# Drone-dimension.net
KiCad netlist of a schematic drawn in EAGLE
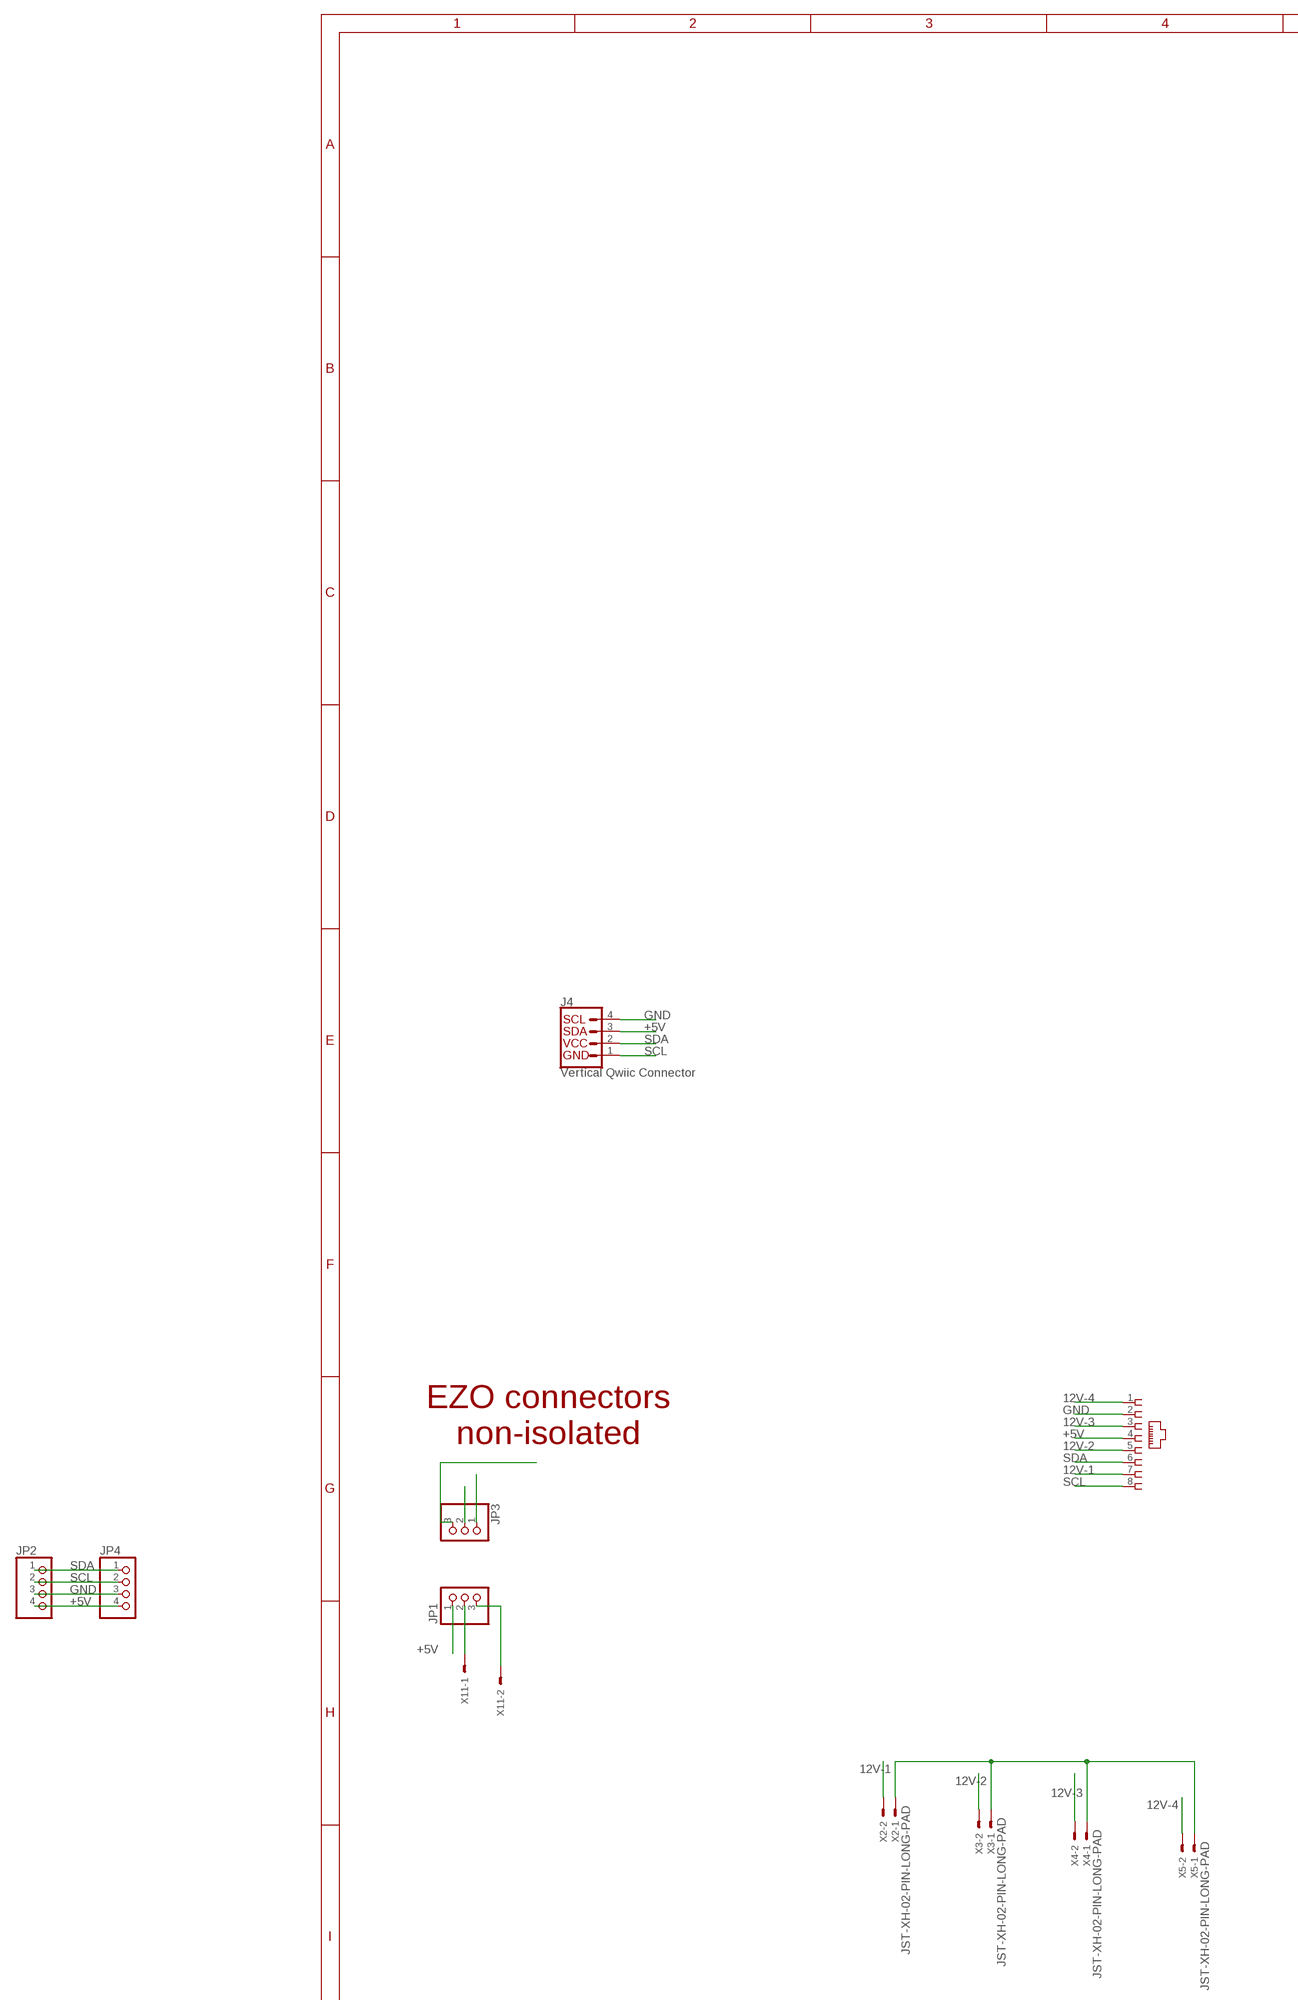
[diagram p0: schematic, sheet 1, part 1 of 2]
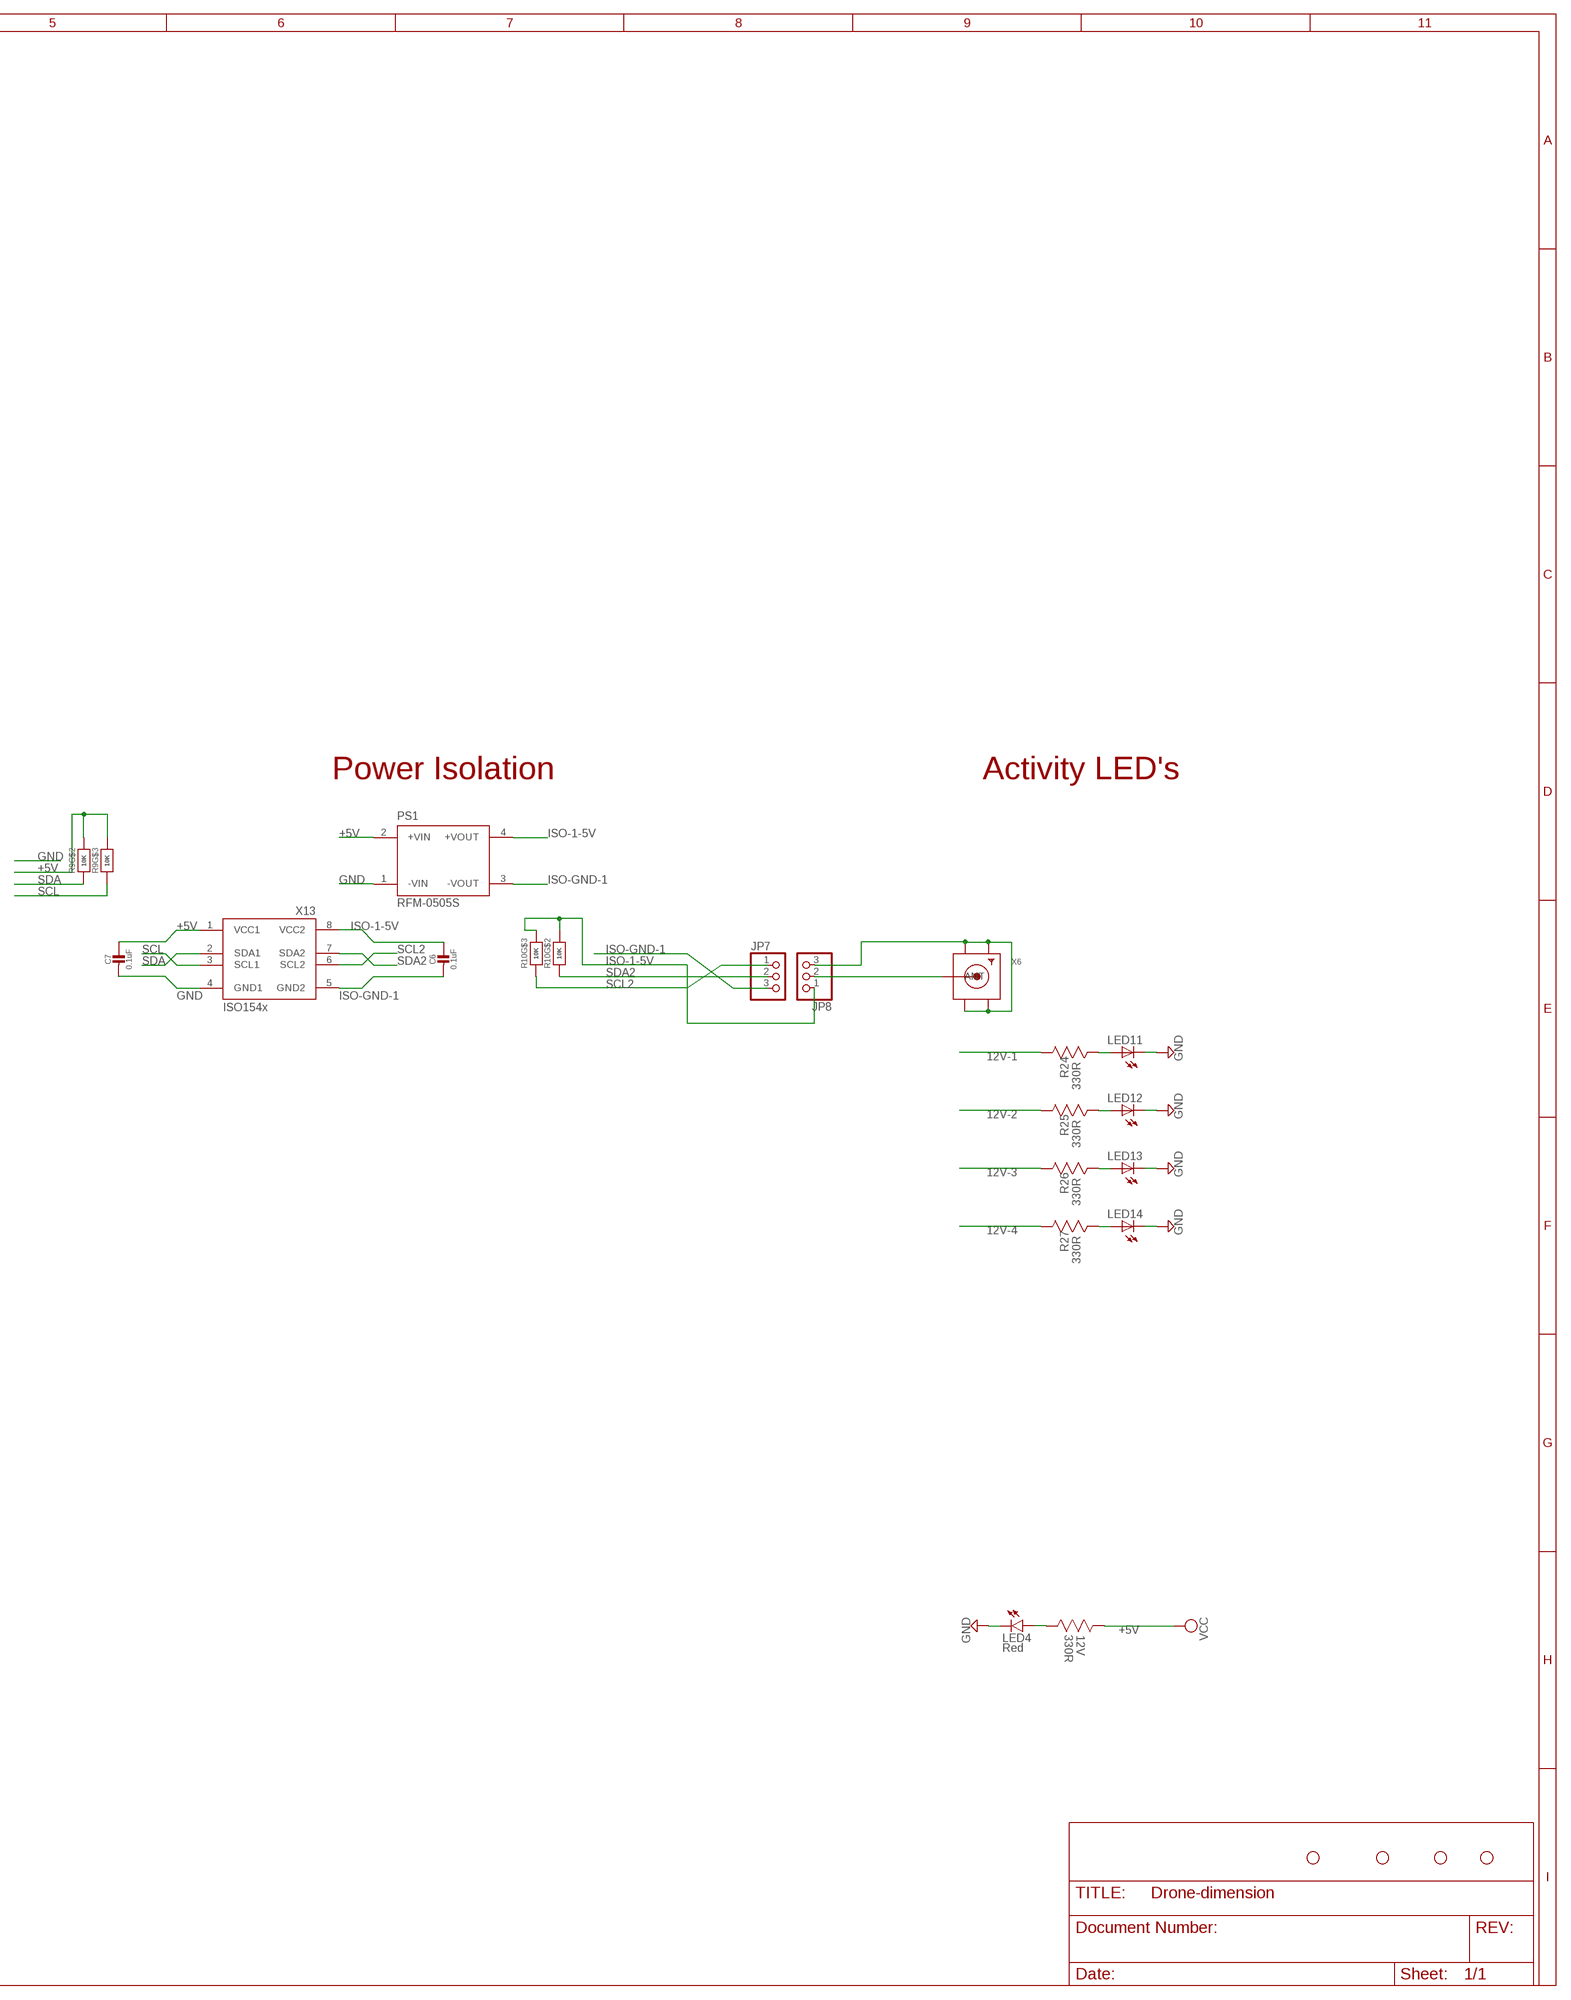
[diagram p1: schematic, sheet 1, part 2 of 2]

(export (version "E")
  (design (tool "Eeschema 10.0.6"))
  (components
    (comp (ref "12V")
      (value "330R")
      (footprint "eagle-import:RESC1608X60N")
      (fields (field (name "MPN") "MC0.063W06031%330R") (field (name "TOLERANCE") "±1%"))
      (libsource (lib "eagle-import") (part "MC0.063W06031%330R"))
    )
    (comp (ref "C6")
      (value "0.1uF")
      (footprint "eagle-import:0603-NO")
      (libsource (lib "eagle-import") (part "CAP_CERAMIC0603_NO"))
    )
    (comp (ref "C7")
      (value "0.1uF")
      (footprint "eagle-import:0603-NO")
      (libsource (lib "eagle-import") (part "CAP_CERAMIC0603_NO"))
    )
    (comp (ref "H5")
      (value "STAND-OFF")
      (footprint "eagle-import:STAND-OFF")
      (libsource (lib "eagle-import") (part "STAND-OFF"))
    )
    (comp (ref "H6")
      (value "STAND-OFF")
      (footprint "eagle-import:STAND-OFF")
      (libsource (lib "eagle-import") (part "STAND-OFF"))
    )
    (comp (ref "H7")
      (value "STAND-OFF")
      (footprint "eagle-import:STAND-OFF")
      (libsource (lib "eagle-import") (part "STAND-OFF"))
    )
    (comp (ref "H8")
      (value "STAND-OFF")
      (footprint "eagle-import:STAND-OFF")
      (libsource (lib "eagle-import") (part "STAND-OFF"))
    )
    (comp (ref "J4")
      (value "Vertical Qwiic Connector")
      (footprint "eagle-import:JST04_1MM_VERT")
      (libsource (lib "eagle-import") (part "QWIIC_CONNECTOR"))
    )
    (comp (ref "JP1")
      (value "PINHD-1X3CB")
      (footprint "eagle-import:1X03-CLEANBIG")
      (libsource (lib "eagle-import") (part "PINHD-1X3CB"))
    )
    (comp (ref "JP2")
      (value "PINHD-1X4")
      (footprint "eagle-import:1X04")
      (libsource (lib "eagle-import") (part "PINHD-1X4"))
    )
    (comp (ref "JP3")
      (value "PINHD-1X3CB")
      (footprint "eagle-import:1X03-CLEANBIG")
      (libsource (lib "eagle-import") (part "PINHD-1X3CB"))
    )
    (comp (ref "JP4")
      (value "PINHD-1X4")
      (footprint "eagle-import:1X04")
      (libsource (lib "eagle-import") (part "PINHD-1X4"))
    )
    (comp (ref "JP7")
      (value "PINHD-1X3CB")
      (footprint "eagle-import:1X03-CLEANBIG")
      (libsource (lib "eagle-import") (part "PINHD-1X3CB"))
    )
    (comp (ref "JP8")
      (value "PINHD-1X3CB")
      (footprint "eagle-import:1X03-CLEANBIG")
      (libsource (lib "eagle-import") (part "PINHD-1X3CB"))
    )
    (comp (ref "LED4")
      (value "Red")
      (footprint "eagle-import:LED-0603")
      (libsource (lib "eagle-import") (part "LED-RED-0603-WE"))
    )
    (comp (ref "LED11")
      (value "BLUE")
      (footprint "eagle-import:CHIPLED_0805")
      (libsource (lib "eagle-import") (part "LEDCHIPLED_0805"))
    )
    (comp (ref "LED12")
      (value "GREEN")
      (footprint "eagle-import:CHIPLED_0805")
      (libsource (lib "eagle-import") (part "LEDCHIPLED_0805"))
    )
    (comp (ref "LED13")
      (value "Yellow")
      (footprint "eagle-import:CHIPLED_0805")
      (libsource (lib "eagle-import") (part "LEDCHIPLED_0805"))
    )
    (comp (ref "LED14")
      (value "RED")
      (footprint "eagle-import:CHIPLED_0805")
      (libsource (lib "eagle-import") (part "LEDCHIPLED_0805"))
    )
    (comp (ref "PS1")
      (value "RFM-0505S")
      (footprint "eagle-import:CONV_RFM-0505S")
      (fields (field (name "MF") "Recom Power"))
      (libsource (lib "eagle-import") (part "RFM-0505S"))
    )
    (comp (ref "PUMPBOX-2")
      (value "RJ45-6L-B")
      (footprint "eagle-import:RJ45-NO-SHIELD")
      (libsource (lib "eagle-import") (part "RJ45-6L-B"))
    )
    (comp (ref "R9")
      (value "10K")
      (footprint "eagle-import:RESPACK_4X0603")
      (libsource (lib "eagle-import") (part "RESISTOR_4PACK"))
    )
    (comp (ref "R10")
      (value "10K")
      (footprint "eagle-import:RESPACK_4X0603")
      (libsource (lib "eagle-import") (part "RESISTOR_4PACK"))
    )
    (comp (ref "R24")
      (value "330R")
      (footprint "eagle-import:RESC1608X60N")
      (fields (field (name "MPN") "MC0.063W06031%330R") (field (name "TOLERANCE") "±1%"))
      (libsource (lib "eagle-import") (part "MC0.063W06031%330R"))
    )
    (comp (ref "R25")
      (value "330R")
      (footprint "eagle-import:RESC1608X60N")
      (fields (field (name "MPN") "MC0.063W06031%330R") (field (name "TOLERANCE") "±1%"))
      (libsource (lib "eagle-import") (part "MC0.063W06031%330R"))
    )
    (comp (ref "R26")
      (value "330R")
      (footprint "eagle-import:RESC1608X60N")
      (fields (field (name "MPN") "MC0.063W06031%330R") (field (name "TOLERANCE") "±1%"))
      (libsource (lib "eagle-import") (part "MC0.063W06031%330R"))
    )
    (comp (ref "R27")
      (value "330R")
      (footprint "eagle-import:RESC1608X60N")
      (fields (field (name "MPN") "MC0.063W06031%330R") (field (name "TOLERANCE") "±1%"))
      (libsource (lib "eagle-import") (part "MC0.063W06031%330R"))
    )
    (comp (ref "X2")
      (value "JST-XH-02-PIN-LONG-PAD")
      (footprint "eagle-import:JST-XH-02-PACKAGE-LONG-PAD")
      (libsource (lib "eagle-import") (part "JST-XH-02-PIN-LONG-PAD"))
    )
    (comp (ref "X3")
      (value "JST-XH-02-PIN-LONG-PAD")
      (footprint "eagle-import:JST-XH-02-PACKAGE-LONG-PAD")
      (libsource (lib "eagle-import") (part "JST-XH-02-PIN-LONG-PAD"))
    )
    (comp (ref "X4")
      (value "JST-XH-02-PIN-LONG-PAD")
      (footprint "eagle-import:JST-XH-02-PACKAGE-LONG-PAD")
      (libsource (lib "eagle-import") (part "JST-XH-02-PIN-LONG-PAD"))
    )
    (comp (ref "X5")
      (value "JST-XH-02-PIN-LONG-PAD")
      (footprint "eagle-import:JST-XH-02-PACKAGE-LONG-PAD")
      (libsource (lib "eagle-import") (part "JST-XH-02-PIN-LONG-PAD"))
    )
    (comp (ref "X6")
      (value "SMACONNECTOR")
      (footprint "eagle-import:SMA90_DIP")
      (libsource (lib "eagle-import") (part "SMACONNECTOR"))
    )
    (comp (ref "X11")
      (value "jst-xh-2")
      (footprint "eagle-import:JST-XH-02-PACKAGE-LONG-PAD")
      (libsource (lib "eagle-import") (part "JST-XH-02-PIN-LONG-PAD"))
    )
    (comp (ref "X13")
      (value "ISO154X")
      (footprint "eagle-import:SOIC8_150MIL")
      (libsource (lib "eagle-import") (part "ISO154X"))
    )
  )
  (nets
    (net (code "1") (name "/12V-1") (class "Default")
      (node (ref "PUMPBOX-2") (pin "7") (pinfunction "7_7") (pintype "passive"))
      (node (ref "R24") (pin "1") (pinfunction "R1_1") (pintype "passive"))
      (node (ref "X2") (pin "2") (pinfunction "S_2") (pintype "passive"))
    )
    (net (code "2") (name "/12V-2") (class "Default")
      (node (ref "PUMPBOX-2") (pin "5") (pinfunction "5_5") (pintype "passive"))
      (node (ref "R25") (pin "1") (pinfunction "R1_1") (pintype "passive"))
      (node (ref "X3") (pin "2") (pinfunction "S_2") (pintype "passive"))
    )
    (net (code "3") (name "/12V-3") (class "Default")
      (node (ref "PUMPBOX-2") (pin "3") (pinfunction "3_3") (pintype "passive"))
      (node (ref "R26") (pin "1") (pinfunction "R1_1") (pintype "passive"))
      (node (ref "X4") (pin "2") (pinfunction "S_2") (pintype "passive"))
    )
    (net (code "4") (name "/12V-4") (class "Default")
      (node (ref "PUMPBOX-2") (pin "1") (pinfunction "1_1") (pintype "passive"))
      (node (ref "R27") (pin "1") (pinfunction "R1_1") (pintype "passive"))
      (node (ref "X5") (pin "2") (pinfunction "S_2") (pintype "passive"))
    )
    (net (code "5") (name "/ISO-1-5V") (class "Default")
      (node (ref "C6") (pin "1") (pinfunction "1_1") (pintype "passive"))
      (node (ref "JP8") (pin "1") (pinfunction "1_1") (pintype "passive"))
      (node (ref "PS1") (pin "4") (pinfunction "+VOUT_4") (pintype "output"))
      (node (ref "R10") (pin "6") (pinfunction "2_6") (pintype "passive"))
      (node (ref "R10") (pin "7") (pinfunction "2_7") (pintype "passive"))
      (node (ref "X13") (pin "8") (pinfunction "VCC2_8") (pintype "power_in"))
    )
    (net (code "6") (name "/ISO-GND-1") (class "Default")
      (node (ref "C6") (pin "2") (pinfunction "2_2") (pintype "passive"))
      (node (ref "JP7") (pin "3") (pinfunction "3_3") (pintype "passive"))
      (node (ref "PS1") (pin "3") (pinfunction "-VOUT_3") (pintype "output"))
      (node (ref "X13") (pin "5") (pinfunction "GND2_5") (pintype "power_in"))
    )
    (net (code "7") (name "/SCL") (class "Default")
      (node (ref "J4") (pin "1") (pinfunction "1_1") (pintype "power_in"))
      (node (ref "JP2") (pin "2") (pinfunction "2_2") (pintype "passive"))
      (node (ref "JP3") (pin "1") (pinfunction "1_1") (pintype "passive"))
      (node (ref "JP4") (pin "2") (pinfunction "2_2") (pintype "passive"))
      (node (ref "PUMPBOX-2") (pin "8") (pinfunction "8_8") (pintype "passive"))
      (node (ref "R9") (pin "3") (pinfunction "1_3") (pintype "passive"))
      (node (ref "X13") (pin "3") (pinfunction "SCL1_3") (pintype "bidirectional"))
    )
    (net (code "8") (name "/SCL2") (class "Default")
      (node (ref "JP7") (pin "1") (pinfunction "1_1") (pintype "passive"))
      (node (ref "R10") (pin "3") (pinfunction "1_3") (pintype "passive"))
      (node (ref "X13") (pin "6") (pinfunction "SCL2_6") (pintype "bidirectional"))
    )
    (net (code "9") (name "/SDA") (class "Default")
      (node (ref "J4") (pin "2") (pinfunction "2_2") (pintype "power_in"))
      (node (ref "JP2") (pin "1") (pinfunction "1_1") (pintype "passive"))
      (node (ref "JP4") (pin "1") (pinfunction "1_1") (pintype "passive"))
      (node (ref "PUMPBOX-2") (pin "6") (pinfunction "6_6") (pintype "passive"))
      (node (ref "R9") (pin "2") (pinfunction "1_2") (pintype "passive"))
      (node (ref "X13") (pin "2") (pinfunction "SDA1_2") (pintype "bidirectional"))
    )
    (net (code "10") (name "/SDA2") (class "Default")
      (node (ref "JP7") (pin "2") (pinfunction "2_2") (pintype "passive"))
      (node (ref "R10") (pin "2") (pinfunction "1_2") (pintype "passive"))
      (node (ref "X13") (pin "7") (pinfunction "SDA2_7") (pintype "bidirectional"))
    )
    (net (code "11") (name "GND") (class "Default")
      (node (ref "C7") (pin "2") (pinfunction "2_2") (pintype "passive"))
      (node (ref "J4") (pin "4") (pinfunction "4_4") (pintype "passive"))
      (node (ref "JP2") (pin "3") (pinfunction "3_3") (pintype "passive"))
      (node (ref "JP3") (pin "3") (pinfunction "3_3") (pintype "passive"))
      (node (ref "JP4") (pin "3") (pinfunction "3_3") (pintype "passive"))
      (node (ref "LED11") (pin "C") (pinfunction "C_C") (pintype "passive"))
      (node (ref "LED12") (pin "C") (pinfunction "C_C") (pintype "passive"))
      (node (ref "LED13") (pin "C") (pinfunction "C_C") (pintype "passive"))
      (node (ref "LED14") (pin "C") (pinfunction "C_C") (pintype "passive"))
      (node (ref "LED4") (pin "C") (pinfunction "C_C") (pintype "passive"))
      (node (ref "PS1") (pin "1") (pinfunction "-VIN_1") (pintype "input"))
      (node (ref "PUMPBOX-2") (pin "2") (pinfunction "2_2") (pintype "passive"))
      (node (ref "X13") (pin "4") (pinfunction "GND1_4") (pintype "power_in"))
      (node (ref "X2") (pin "1") (pinfunction "S_1") (pintype "passive"))
      (node (ref "X3") (pin "1") (pinfunction "S_1") (pintype "passive"))
      (node (ref "X4") (pin "1") (pinfunction "S_1") (pintype "passive"))
      (node (ref "X5") (pin "1") (pinfunction "S_1") (pintype "passive"))
    )
    (net (code "12") (name "Net-(12V-R2)") (class "Default")
      (node (ref "12V") (pin "2") (pinfunction "R2_2") (pintype "passive"))
      (node (ref "LED4") (pin "A") (pinfunction "A_A") (pintype "passive"))
    )
    (net (code "13") (name "Net-(JP8-Pad3)") (class "Default")
      (node (ref "JP8") (pin "3") (pinfunction "3_3") (pintype "passive"))
      (node (ref "X6") (pin "GND1") (pinfunction "GND1_GND1") (pintype "power_in"))
      (node (ref "X6") (pin "GND2") (pinfunction "GND2_GND2") (pintype "power_in"))
      (node (ref "X6") (pin "GND3") (pinfunction "GND3_GND3") (pintype "power_in"))
      (node (ref "X6") (pin "GND4") (pinfunction "GND4_GND4") (pintype "power_in"))
    )
    (net (code "14") (name "Net-(R24-R2)") (class "Default")
      (node (ref "LED11") (pin "A") (pinfunction "A_A") (pintype "passive"))
      (node (ref "R24") (pin "2") (pinfunction "R2_2") (pintype "passive"))
    )
    (net (code "15") (name "Net-(R25-R2)") (class "Default")
      (node (ref "LED12") (pin "A") (pinfunction "A_A") (pintype "passive"))
      (node (ref "R25") (pin "2") (pinfunction "R2_2") (pintype "passive"))
    )
    (net (code "16") (name "Net-(R26-R2)") (class "Default")
      (node (ref "LED13") (pin "A") (pinfunction "A_A") (pintype "passive"))
      (node (ref "R26") (pin "2") (pinfunction "R2_2") (pintype "passive"))
    )
    (net (code "17") (name "Net-(R27-R2)") (class "Default")
      (node (ref "LED14") (pin "A") (pinfunction "A_A") (pintype "passive"))
      (node (ref "R27") (pin "2") (pinfunction "R2_2") (pintype "passive"))
    )
    (net (code "18") (name "Net-(X6-ANT)") (class "Default")
      (node (ref "JP8") (pin "2") (pinfunction "2_2") (pintype "passive"))
      (node (ref "X6") (pin "ANTENNA") (pinfunction "ANT_ANTENNA") (pintype "bidirectional"))
    )
    (net (code "19") (name "Net-(X11A-S)") (class "Default")
      (node (ref "JP1") (pin "2") (pinfunction "2_2") (pintype "passive"))
      (node (ref "X11") (pin "1") (pinfunction "S_1") (pintype "passive"))
    )
    (net (code "20") (name "Net-(X11B-S)") (class "Default")
      (node (ref "JP1") (pin "3") (pinfunction "3_3") (pintype "passive"))
      (node (ref "X11") (pin "2") (pinfunction "S_2") (pintype "passive"))
    )
    (net (code "21") (name "VCC") (class "Default")
      (node (ref "12V") (pin "1") (pinfunction "R1_1") (pintype "passive"))
      (node (ref "C7") (pin "1") (pinfunction "1_1") (pintype "passive"))
      (node (ref "J4") (pin "3") (pinfunction "3_3") (pintype "passive"))
      (node (ref "JP1") (pin "1") (pinfunction "1_1") (pintype "passive"))
      (node (ref "JP2") (pin "4") (pinfunction "4_4") (pintype "passive"))
      (node (ref "JP4") (pin "4") (pinfunction "4_4") (pintype "passive"))
      (node (ref "PS1") (pin "2") (pinfunction "+VIN_2") (pintype "input"))
      (node (ref "PUMPBOX-2") (pin "4") (pinfunction "4_4") (pintype "passive"))
      (node (ref "R9") (pin "6") (pinfunction "2_6") (pintype "passive"))
      (node (ref "R9") (pin "7") (pinfunction "2_7") (pintype "passive"))
      (node (ref "X13") (pin "1") (pinfunction "VCC1_1") (pintype "power_in"))
    )
    (net (code "22") (name "unconnected-(JP3-Pad2)") (class "Default")
      (node (ref "JP3") (pin "2") (pinfunction "2_2") (pintype "passive"))
    )
  )
)
